# Sheet1.net
KiCad netlist of a schematic drawn in Altium Designer
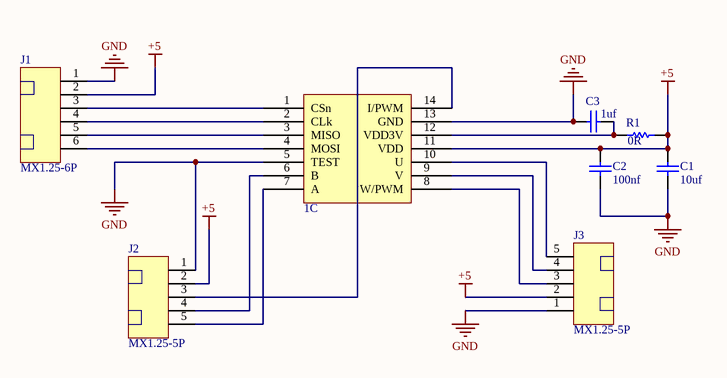
[diagram p0: Sheet1.SchDoc]

(export (version "E")
  (design (tool "Eeschema 10.0.6"))
  (components
    (comp (ref "1") (value "AS5147P") (footprint "TSSOP14MAX") (libsource (lib "Schlib1") (part "AS5147P")))
    (comp (ref "C1")
      (value "10uf")
      (footprint "0805C")
      (description "Capacitor")
      (fields (field (name "Comment") "Cap") (field (name "PUBLISHER") "Altium Limited"))
      (libsource (lib "Miscellaneous Devices") (part "Cap"))
    )
    (comp (ref "C2")
      (value "100nf")
      (footprint "0603C")
      (description "Capacitor")
      (fields (field (name "Comment") "Cap") (field (name "PUBLISHER") "Altium Limited"))
      (libsource (lib "Miscellaneous Devices") (part "Cap"))
    )
    (comp (ref "C3")
      (value "1uf")
      (footprint "0603C")
      (description "Capacitor")
      (fields (field (name "Comment") "Cap") (field (name "PUBLISHER") "Altium Limited"))
      (libsource (lib "Miscellaneous Devices") (part "Cap"))
    )
    (comp (ref "J1") (value "MX1.25-6P") (footprint "MX1.25-6P") (libsource (lib "MX") (part "MX1.25-6P")))
    (comp (ref "J2") (value "MX1.25-5P") (footprint "MX1.25-5P") (libsource (lib "") (part "MX1.25-5P_1")))
    (comp (ref "J3") (value "MX1.25-5P") (footprint "MX1.25-5P") (libsource (lib "MX") (part "MX1.25-5P")))
    (comp (ref "R1")
      (value "0R")
      (footprint "0603R")
      (description "Resistor")
      (fields (field (name "Comment") "Res1") (field (name "PUBLISHER") "Altium Limited"))
      (libsource (lib "Miscellaneous Devices") (part "Res1"))
    )
  )
  (nets
    (net (code "1") (name "+5") (class "Default")
      (node (ref "1") (pin "11") (pinfunction "VDD_11") (pintype "passive"))
      (node (ref "C1") (pin "2") (pinfunction "2_2") (pintype "passive"))
      (node (ref "C2") (pin "2") (pinfunction "2_2") (pintype "passive"))
      (node (ref "J1") (pin "2") (pinfunction "2_2") (pintype "passive"))
      (node (ref "J2") (pin "2") (pinfunction "2_2") (pintype "passive"))
      (node (ref "J3") (pin "2") (pinfunction "2_2") (pintype "passive"))
      (node (ref "R1") (pin "2") (pinfunction "2_2") (pintype "passive"))
    )
    (net (code "2") (name "GND") (class "Default")
      (node (ref "1") (pin "13") (pinfunction "GND_13") (pintype "passive"))
      (node (ref "1") (pin "5") (pinfunction "TEST_5") (pintype "passive"))
      (node (ref "C1") (pin "1") (pinfunction "1_1") (pintype "passive"))
      (node (ref "C2") (pin "1") (pinfunction "1_1") (pintype "passive"))
      (node (ref "C3") (pin "2") (pinfunction "2_2") (pintype "passive"))
      (node (ref "J1") (pin "1") (pinfunction "1_1") (pintype "passive"))
      (node (ref "J2") (pin "1") (pinfunction "1_1") (pintype "passive"))
      (node (ref "J3") (pin "1") (pinfunction "1_1") (pintype "passive"))
    )
    (net (code "3") (name "Net-(1C-A)") (class "Default")
      (node (ref "1") (pin "7") (pinfunction "A_7") (pintype "passive"))
      (node (ref "J2") (pin "5") (pinfunction "5_5") (pintype "passive"))
    )
    (net (code "4") (name "Net-(1C-B)") (class "Default")
      (node (ref "1") (pin "6") (pinfunction "B_6") (pintype "passive"))
      (node (ref "J2") (pin "4") (pinfunction "4_4") (pintype "passive"))
    )
    (net (code "5") (name "Net-(1C-CLk)") (class "Default")
      (node (ref "1") (pin "2") (pinfunction "CLk_2") (pintype "passive"))
      (node (ref "J1") (pin "4") (pinfunction "4_4") (pintype "passive"))
    )
    (net (code "6") (name "Net-(1C-CSn)") (class "Default")
      (node (ref "1") (pin "1") (pinfunction "CSn_1") (pintype "passive"))
      (node (ref "J1") (pin "3") (pinfunction "3_3") (pintype "passive"))
    )
    (net (code "7") (name "Net-(1C-I{slash}PWM)") (class "Default")
      (node (ref "1") (pin "14") (pinfunction "I/PWM_14") (pintype "passive"))
      (node (ref "J2") (pin "3") (pinfunction "3_3") (pintype "passive"))
    )
    (net (code "8") (name "Net-(1C-MISO)") (class "Default")
      (node (ref "1") (pin "3") (pinfunction "MISO_3") (pintype "passive"))
      (node (ref "J1") (pin "5") (pinfunction "5_5") (pintype "passive"))
    )
    (net (code "9") (name "Net-(1C-MOSI)") (class "Default")
      (node (ref "1") (pin "4") (pinfunction "MOSI_4") (pintype "passive"))
      (node (ref "J1") (pin "6") (pinfunction "6_6") (pintype "passive"))
    )
    (net (code "10") (name "Net-(1C-U)") (class "Default")
      (node (ref "1") (pin "10") (pinfunction "U_10") (pintype "passive"))
      (node (ref "J3") (pin "5") (pinfunction "5_5") (pintype "passive"))
    )
    (net (code "11") (name "Net-(1C-V)") (class "Default")
      (node (ref "1") (pin "9") (pinfunction "V_9") (pintype "passive"))
      (node (ref "J3") (pin "4") (pinfunction "4_4") (pintype "passive"))
    )
    (net (code "12") (name "Net-(1C-VDD3V)") (class "Default")
      (node (ref "1") (pin "12") (pinfunction "VDD3V_12") (pintype "passive"))
      (node (ref "C3") (pin "1") (pinfunction "1_1") (pintype "passive"))
      (node (ref "R1") (pin "1") (pinfunction "1_1") (pintype "passive"))
    )
    (net (code "13") (name "Net-(1C-W{slash}PWM)") (class "Default")
      (node (ref "1") (pin "8") (pinfunction "W/PWM_8") (pintype "passive"))
      (node (ref "J3") (pin "3") (pinfunction "3_3") (pintype "passive"))
    )
  )
)
